# AS3364_bus_mixer_v1_0.net
KiCad netlist of a schematic drawn in EAGLE
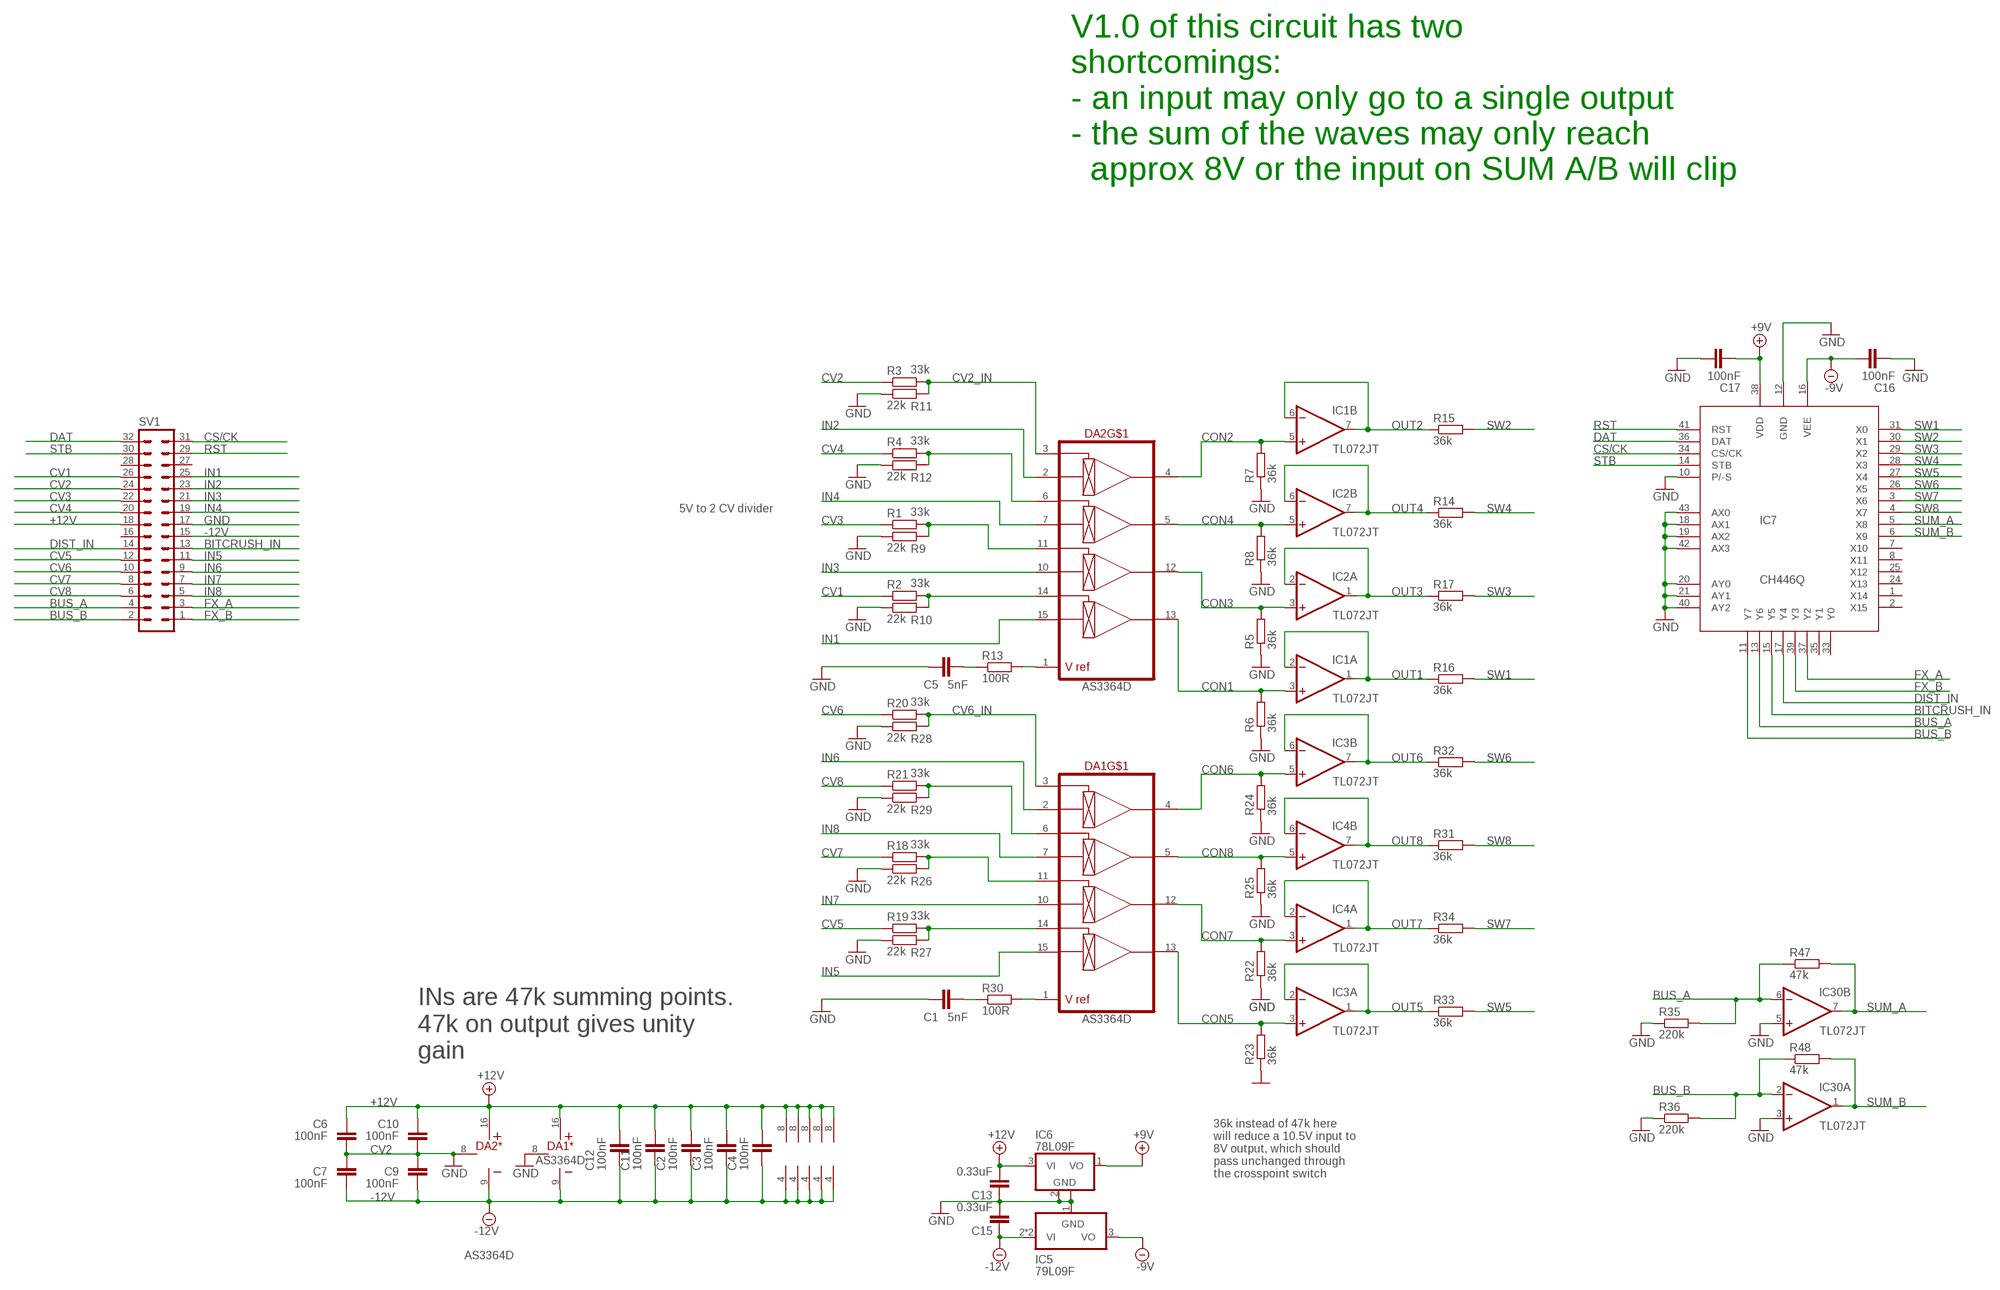
[diagram p0: schematic, sheet 1]

(export (version "E")
  (design (tool "Eeschema 10.0.6"))
  (components
    (comp (ref "C1")
      (value "5nF")
      (footprint "eagle-import:C0402")
      (libsource (lib "eagle-import") (part "C-EUC0402"))
    )
    (comp (ref "C2")
      (value "100nF")
      (footprint "eagle-import:C0402")
      (libsource (lib "eagle-import") (part "C-EUC0402"))
    )
    (comp (ref "C3")
      (value "100nF")
      (footprint "eagle-import:C0402")
      (libsource (lib "eagle-import") (part "C-EUC0402"))
    )
    (comp (ref "C4")
      (value "100nF")
      (footprint "eagle-import:C0402")
      (libsource (lib "eagle-import") (part "C-EUC0402"))
    )
    (comp (ref "C5")
      (value "5nF")
      (footprint "eagle-import:C0402")
      (libsource (lib "eagle-import") (part "C-EUC0402"))
    )
    (comp (ref "C6")
      (value "100nF")
      (footprint "eagle-import:C0402")
      (libsource (lib "eagle-import") (part "C-EUC0402"))
    )
    (comp (ref "C7")
      (value "100nF")
      (footprint "eagle-import:C0402")
      (libsource (lib "eagle-import") (part "C-EUC0402"))
    )
    (comp (ref "C9")
      (value "100nF")
      (footprint "eagle-import:C0402")
      (libsource (lib "eagle-import") (part "C-EUC0402"))
    )
    (comp (ref "C10")
      (value "100nF")
      (footprint "eagle-import:C0402")
      (libsource (lib "eagle-import") (part "C-EUC0402"))
    )
    (comp (ref "C11")
      (value "100nF")
      (footprint "eagle-import:C0402")
      (libsource (lib "eagle-import") (part "C-EUC0402"))
    )
    (comp (ref "C12")
      (value "100nF")
      (footprint "eagle-import:C0402")
      (libsource (lib "eagle-import") (part "C-EUC0402"))
    )
    (comp (ref "C13")
      (value "0.33uF")
      (footprint "eagle-import:C0603")
      (libsource (lib "eagle-import") (part "resistor_C-EUC0603"))
    )
    (comp (ref "C15")
      (value "0.33uF")
      (footprint "eagle-import:C0603")
      (libsource (lib "eagle-import") (part "resistor_C-EUC0603"))
    )
    (comp (ref "C16")
      (value "100nF")
      (footprint "eagle-import:C0402")
      (libsource (lib "eagle-import") (part "C-EUC0402"))
    )
    (comp (ref "C17")
      (value "100nF")
      (footprint "eagle-import:C0402")
      (libsource (lib "eagle-import") (part "C-EUC0402"))
    )
    (comp (ref "DA1")
      (value "AS3364D")
      (footprint "eagle-import:DIL16J")
      (libsource (lib "eagle-import") (part "AS3364D"))
    )
    (comp (ref "DA2")
      (value "AS3364D")
      (footprint "eagle-import:DIL16J")
      (libsource (lib "eagle-import") (part "AS3364D"))
    )
    (comp (ref "IC1")
      (value "TL072JT")
      (footprint "eagle-import:TSSOP8J")
      (libsource (lib "eagle-import") (part "TL072JT"))
    )
    (comp (ref "IC2")
      (value "TL072JT")
      (footprint "eagle-import:TSSOP8J")
      (libsource (lib "eagle-import") (part "TL072JT"))
    )
    (comp (ref "IC3")
      (value "TL072JT")
      (footprint "eagle-import:TSSOP8J")
      (libsource (lib "eagle-import") (part "TL072JT"))
    )
    (comp (ref "IC4")
      (value "TL072JT")
      (footprint "eagle-import:TSSOP8J")
      (libsource (lib "eagle-import") (part "TL072JT"))
    )
    (comp (ref "IC5")
      (value "79L09F")
      (footprint "eagle-import:SOT89")
      (libsource (lib "eagle-import") (part "79LF09"))
    )
    (comp (ref "IC6")
      (value "78L09F")
      (footprint "eagle-import:SOT89")
      (libsource (lib "eagle-import") (part "78LF09"))
    )
    (comp (ref "IC7")
      (value "CH446Q")
      (footprint "eagle-import:LQFP-44-J")
      (libsource (lib "eagle-import") (part "CH446Q"))
    )
    (comp (ref "IC30")
      (value "TL072JT")
      (footprint "eagle-import:TSSOP8J")
      (libsource (lib "eagle-import") (part "TL072JT"))
    )
    (comp (ref "R1")
      (value "33k")
      (footprint "eagle-import:R0402")
      (libsource (lib "eagle-import") (part "R-EU_R0402"))
    )
    (comp (ref "R2")
      (value "33k")
      (footprint "eagle-import:R0402")
      (libsource (lib "eagle-import") (part "R-EU_R0402"))
    )
    (comp (ref "R3")
      (value "33k")
      (footprint "eagle-import:R0402")
      (libsource (lib "eagle-import") (part "R-EU_R0402"))
    )
    (comp (ref "R4")
      (value "33k")
      (footprint "eagle-import:R0402")
      (libsource (lib "eagle-import") (part "R-EU_R0402"))
    )
    (comp (ref "R5")
      (value "36k")
      (footprint "eagle-import:R0402")
      (libsource (lib "eagle-import") (part "R-EU_R0402"))
    )
    (comp (ref "R6")
      (value "36k")
      (footprint "eagle-import:R0402")
      (libsource (lib "eagle-import") (part "R-EU_R0402"))
    )
    (comp (ref "R7")
      (value "36k")
      (footprint "eagle-import:R0402")
      (libsource (lib "eagle-import") (part "R-EU_R0402"))
    )
    (comp (ref "R8")
      (value "36k")
      (footprint "eagle-import:R0402")
      (libsource (lib "eagle-import") (part "R-EU_R0402"))
    )
    (comp (ref "R9")
      (value "22k")
      (footprint "eagle-import:R0402")
      (libsource (lib "eagle-import") (part "R-EU_R0402"))
    )
    (comp (ref "R10")
      (value "22k")
      (footprint "eagle-import:R0402")
      (libsource (lib "eagle-import") (part "R-EU_R0402"))
    )
    (comp (ref "R11")
      (value "22k")
      (footprint "eagle-import:R0402")
      (libsource (lib "eagle-import") (part "R-EU_R0402"))
    )
    (comp (ref "R12")
      (value "22k")
      (footprint "eagle-import:R0402")
      (libsource (lib "eagle-import") (part "R-EU_R0402"))
    )
    (comp (ref "R13")
      (value "100R")
      (footprint "eagle-import:R0402")
      (libsource (lib "eagle-import") (part "R-EU_R0402"))
    )
    (comp (ref "R14")
      (value "36k")
      (footprint "eagle-import:R0402")
      (libsource (lib "eagle-import") (part "R-EU_R0402"))
    )
    (comp (ref "R15")
      (value "36k")
      (footprint "eagle-import:R0402")
      (libsource (lib "eagle-import") (part "R-EU_R0402"))
    )
    (comp (ref "R16")
      (value "36k")
      (footprint "eagle-import:R0402")
      (libsource (lib "eagle-import") (part "R-EU_R0402"))
    )
    (comp (ref "R17")
      (value "36k")
      (footprint "eagle-import:R0402")
      (libsource (lib "eagle-import") (part "R-EU_R0402"))
    )
    (comp (ref "R18")
      (value "33k")
      (footprint "eagle-import:R0402")
      (libsource (lib "eagle-import") (part "R-EU_R0402"))
    )
    (comp (ref "R19")
      (value "33k")
      (footprint "eagle-import:R0402")
      (libsource (lib "eagle-import") (part "R-EU_R0402"))
    )
    (comp (ref "R20")
      (value "33k")
      (footprint "eagle-import:R0402")
      (libsource (lib "eagle-import") (part "R-EU_R0402"))
    )
    (comp (ref "R21")
      (value "33k")
      (footprint "eagle-import:R0402")
      (libsource (lib "eagle-import") (part "R-EU_R0402"))
    )
    (comp (ref "R22")
      (value "36k")
      (footprint "eagle-import:R0402")
      (libsource (lib "eagle-import") (part "R-EU_R0402"))
    )
    (comp (ref "R23")
      (value "36k")
      (footprint "eagle-import:R0402")
      (libsource (lib "eagle-import") (part "R-EU_R0402"))
    )
    (comp (ref "R24")
      (value "36k")
      (footprint "eagle-import:R0402")
      (libsource (lib "eagle-import") (part "R-EU_R0402"))
    )
    (comp (ref "R25")
      (value "36k")
      (footprint "eagle-import:R0402")
      (libsource (lib "eagle-import") (part "R-EU_R0402"))
    )
    (comp (ref "R26")
      (value "22k")
      (footprint "eagle-import:R0402")
      (libsource (lib "eagle-import") (part "R-EU_R0402"))
    )
    (comp (ref "R27")
      (value "22k")
      (footprint "eagle-import:R0402")
      (libsource (lib "eagle-import") (part "R-EU_R0402"))
    )
    (comp (ref "R28")
      (value "22k")
      (footprint "eagle-import:R0402")
      (libsource (lib "eagle-import") (part "R-EU_R0402"))
    )
    (comp (ref "R29")
      (value "22k")
      (footprint "eagle-import:R0402")
      (libsource (lib "eagle-import") (part "R-EU_R0402"))
    )
    (comp (ref "R30")
      (value "100R")
      (footprint "eagle-import:R0402")
      (libsource (lib "eagle-import") (part "R-EU_R0402"))
    )
    (comp (ref "R31")
      (value "36k")
      (footprint "eagle-import:R0402")
      (libsource (lib "eagle-import") (part "R-EU_R0402"))
    )
    (comp (ref "R32")
      (value "36k")
      (footprint "eagle-import:R0402")
      (libsource (lib "eagle-import") (part "R-EU_R0402"))
    )
    (comp (ref "R33")
      (value "36k")
      (footprint "eagle-import:R0402")
      (libsource (lib "eagle-import") (part "R-EU_R0402"))
    )
    (comp (ref "R34")
      (value "36k")
      (footprint "eagle-import:R0402")
      (libsource (lib "eagle-import") (part "R-EU_R0402"))
    )
    (comp (ref "R35")
      (value "220k")
      (footprint "eagle-import:R0402")
      (libsource (lib "eagle-import") (part "R-EU_R0402"))
    )
    (comp (ref "R36")
      (value "220k")
      (footprint "eagle-import:R0402")
      (libsource (lib "eagle-import") (part "R-EU_R0402"))
    )
    (comp (ref "R47")
      (value "47k")
      (footprint "eagle-import:R0402")
      (libsource (lib "eagle-import") (part "R-EU_R0402"))
    )
    (comp (ref "R48")
      (value "47k")
      (footprint "eagle-import:R0402")
      (libsource (lib "eagle-import") (part "R-EU_R0402"))
    )
    (comp (ref "SV1")
      (value "MA16-2WJ")
      (footprint "eagle-import:MA16-2WJ")
      (libsource (lib "eagle-import") (part "MA16-2WJ"))
    )
  )
  (nets
    (net (code "1") (name "+9V") (class "Default")
      (node (ref "C17") (pin "1") (pinfunction "1_1") (pintype "passive"))
      (node (ref "IC6") (pin "1") (pinfunction "VO_1") (pintype "passive"))
      (node (ref "IC7") (pin "38") (pinfunction "VDD_38") (pintype "power_in"))
    )
    (net (code "2") (name "+12V") (class "Default")
      (node (ref "C10") (pin "2") (pinfunction "2_2") (pintype "passive"))
      (node (ref "C11") (pin "2") (pinfunction "2_2") (pintype "passive"))
      (node (ref "C12") (pin "2") (pinfunction "2_2") (pintype "passive"))
      (node (ref "C13") (pin "2") (pinfunction "2_2") (pintype "passive"))
      (node (ref "C2") (pin "2") (pinfunction "2_2") (pintype "passive"))
      (node (ref "C3") (pin "2") (pinfunction "2_2") (pintype "passive"))
      (node (ref "C4") (pin "2") (pinfunction "2_2") (pintype "passive"))
      (node (ref "C6") (pin "2") (pinfunction "2_2") (pintype "passive"))
      (node (ref "DA1") (pin "16") (pinfunction "V+_16") (pintype "power_in"))
      (node (ref "DA2") (pin "16") (pinfunction "V+_16") (pintype "power_in"))
      (node (ref "IC1") (pin "8") (pinfunction "V+_8") (pintype "power_in"))
      (node (ref "IC2") (pin "8") (pinfunction "V+_8") (pintype "power_in"))
      (node (ref "IC3") (pin "8") (pinfunction "V+_8") (pintype "power_in"))
      (node (ref "IC30") (pin "8") (pinfunction "V+_8") (pintype "power_in"))
      (node (ref "IC4") (pin "8") (pinfunction "V+_8") (pintype "power_in"))
      (node (ref "IC6") (pin "3") (pinfunction "VI_3") (pintype "input"))
      (node (ref "SV1") (pin "18") (pinfunction "18_18") (pintype "passive"))
    )
    (net (code "3") (name "-9V") (class "Default")
      (node (ref "C16") (pin "2") (pinfunction "2_2") (pintype "passive"))
      (node (ref "IC5") (pin "3") (pinfunction "VO_3") (pintype "passive"))
      (node (ref "IC7") (pin "16") (pinfunction "VEE_16") (pintype "power_in"))
    )
    (net (code "4") (name "-12V") (class "Default")
      (node (ref "C11") (pin "1") (pinfunction "1_1") (pintype "passive"))
      (node (ref "C12") (pin "1") (pinfunction "1_1") (pintype "passive"))
      (node (ref "C15") (pin "1") (pinfunction "1_1") (pintype "passive"))
      (node (ref "C2") (pin "1") (pinfunction "1_1") (pintype "passive"))
      (node (ref "C3") (pin "1") (pinfunction "1_1") (pintype "passive"))
      (node (ref "C4") (pin "1") (pinfunction "1_1") (pintype "passive"))
      (node (ref "C7") (pin "1") (pinfunction "1_1") (pintype "passive"))
      (node (ref "C9") (pin "1") (pinfunction "1_1") (pintype "passive"))
      (node (ref "DA1") (pin "9") (pinfunction "V-_9") (pintype "power_in"))
      (node (ref "DA2") (pin "9") (pinfunction "V-_9") (pintype "power_in"))
      (node (ref "IC1") (pin "4") (pinfunction "V-_4") (pintype "power_in"))
      (node (ref "IC2") (pin "4") (pinfunction "V-_4") (pintype "power_in"))
      (node (ref "IC3") (pin "4") (pinfunction "V-_4") (pintype "power_in"))
      (node (ref "IC30") (pin "4") (pinfunction "V-_4") (pintype "power_in"))
      (node (ref "IC4") (pin "4") (pinfunction "V-_4") (pintype "power_in"))
      (node (ref "IC5") (pin "2") (pinfunction "VI_2") (pintype "input"))
      (node (ref "IC5") (pin "2@1") (pinfunction "VI_2@1") (pintype "input"))
      (node (ref "SV1") (pin "15") (pinfunction "15_15") (pintype "passive"))
    )
    (net (code "5") (name "/BITCRUSH_IN") (class "Default")
      (node (ref "IC7") (pin "15") (pinfunction "Y5_15") (pintype "bidirectional"))
      (node (ref "SV1") (pin "13") (pinfunction "13_13") (pintype "passive"))
    )
    (net (code "6") (name "/BUS_A") (class "Default")
      (node (ref "IC30") (pin "6") (pinfunction "-IN_6") (pintype "input"))
      (node (ref "IC7") (pin "13") (pinfunction "Y6_13") (pintype "bidirectional"))
      (node (ref "R35") (pin "2") (pinfunction "2_2") (pintype "passive"))
      (node (ref "R47") (pin "1") (pinfunction "1_1") (pintype "passive"))
      (node (ref "SV1") (pin "4") (pinfunction "4_4") (pintype "passive"))
    )
    (net (code "7") (name "/BUS_B") (class "Default")
      (node (ref "IC30") (pin "2") (pinfunction "-IN_2") (pintype "input"))
      (node (ref "IC7") (pin "11") (pinfunction "Y7_11") (pintype "bidirectional"))
      (node (ref "R36") (pin "2") (pinfunction "2_2") (pintype "passive"))
      (node (ref "R48") (pin "1") (pinfunction "1_1") (pintype "passive"))
      (node (ref "SV1") (pin "2") (pinfunction "2_2") (pintype "passive"))
    )
    (net (code "8") (name "/CON1") (class "Default")
      (node (ref "DA2") (pin "13") (pinfunction "OUT4_13") (pintype "output"))
      (node (ref "IC1") (pin "3") (pinfunction "+IN_3") (pintype "input"))
      (node (ref "R6") (pin "2") (pinfunction "2_2") (pintype "passive"))
    )
    (net (code "9") (name "/CON2") (class "Default")
      (node (ref "DA2") (pin "4") (pinfunction "OUT1_4") (pintype "output"))
      (node (ref "IC1") (pin "5") (pinfunction "+IN_5") (pintype "input"))
      (node (ref "R7") (pin "2") (pinfunction "2_2") (pintype "passive"))
    )
    (net (code "10") (name "/CON3") (class "Default")
      (node (ref "DA2") (pin "12") (pinfunction "OUT3_12") (pintype "output"))
      (node (ref "IC2") (pin "3") (pinfunction "+IN_3") (pintype "input"))
      (node (ref "R5") (pin "2") (pinfunction "2_2") (pintype "passive"))
    )
    (net (code "11") (name "/CON4") (class "Default")
      (node (ref "DA2") (pin "5") (pinfunction "OUT2_5") (pintype "output"))
      (node (ref "IC2") (pin "5") (pinfunction "+IN_5") (pintype "input"))
      (node (ref "R8") (pin "2") (pinfunction "2_2") (pintype "passive"))
    )
    (net (code "12") (name "/CON5") (class "Default")
      (node (ref "DA1") (pin "13") (pinfunction "OUT4_13") (pintype "output"))
      (node (ref "IC3") (pin "3") (pinfunction "+IN_3") (pintype "input"))
      (node (ref "R23") (pin "2") (pinfunction "2_2") (pintype "passive"))
    )
    (net (code "13") (name "/CON6") (class "Default")
      (node (ref "DA1") (pin "4") (pinfunction "OUT1_4") (pintype "output"))
      (node (ref "IC3") (pin "5") (pinfunction "+IN_5") (pintype "input"))
      (node (ref "R24") (pin "2") (pinfunction "2_2") (pintype "passive"))
    )
    (net (code "14") (name "/CON7") (class "Default")
      (node (ref "DA1") (pin "12") (pinfunction "OUT3_12") (pintype "output"))
      (node (ref "IC4") (pin "3") (pinfunction "+IN_3") (pintype "input"))
      (node (ref "R22") (pin "2") (pinfunction "2_2") (pintype "passive"))
    )
    (net (code "15") (name "/CON8") (class "Default")
      (node (ref "DA1") (pin "5") (pinfunction "OUT2_5") (pintype "output"))
      (node (ref "IC4") (pin "5") (pinfunction "+IN_5") (pintype "input"))
      (node (ref "R25") (pin "2") (pinfunction "2_2") (pintype "passive"))
    )
    (net (code "16") (name "/CS{slash}CK") (class "Default")
      (node (ref "IC7") (pin "34") (pinfunction "CS/CK_34") (pintype "bidirectional"))
      (node (ref "SV1") (pin "31") (pinfunction "31_31") (pintype "passive"))
    )
    (net (code "17") (name "/CV1") (class "Default")
      (node (ref "R2") (pin "1") (pinfunction "1_1") (pintype "passive"))
      (node (ref "SV1") (pin "26") (pinfunction "26_26") (pintype "passive"))
    )
    (net (code "18") (name "/CV2") (class "Default")
      (node (ref "R3") (pin "1") (pinfunction "1_1") (pintype "passive"))
      (node (ref "SV1") (pin "24") (pinfunction "24_24") (pintype "passive"))
    )
    (net (code "19") (name "/CV2_IN") (class "Default")
      (node (ref "DA2") (pin "3") (pinfunction "CV1_3") (pintype "input"))
      (node (ref "R11") (pin "2") (pinfunction "2_2") (pintype "passive"))
      (node (ref "R3") (pin "2") (pinfunction "2_2") (pintype "passive"))
    )
    (net (code "20") (name "/CV3") (class "Default")
      (node (ref "R1") (pin "1") (pinfunction "1_1") (pintype "passive"))
      (node (ref "SV1") (pin "22") (pinfunction "22_22") (pintype "passive"))
    )
    (net (code "21") (name "/CV4") (class "Default")
      (node (ref "R4") (pin "1") (pinfunction "1_1") (pintype "passive"))
      (node (ref "SV1") (pin "20") (pinfunction "20_20") (pintype "passive"))
    )
    (net (code "22") (name "/CV5") (class "Default")
      (node (ref "R19") (pin "1") (pinfunction "1_1") (pintype "passive"))
      (node (ref "SV1") (pin "12") (pinfunction "12_12") (pintype "passive"))
    )
    (net (code "23") (name "/CV6") (class "Default")
      (node (ref "R20") (pin "1") (pinfunction "1_1") (pintype "passive"))
      (node (ref "SV1") (pin "10") (pinfunction "10_10") (pintype "passive"))
    )
    (net (code "24") (name "/CV6_IN") (class "Default")
      (node (ref "DA1") (pin "3") (pinfunction "CV1_3") (pintype "input"))
      (node (ref "R20") (pin "2") (pinfunction "2_2") (pintype "passive"))
      (node (ref "R28") (pin "2") (pinfunction "2_2") (pintype "passive"))
    )
    (net (code "25") (name "/CV7") (class "Default")
      (node (ref "R18") (pin "1") (pinfunction "1_1") (pintype "passive"))
      (node (ref "SV1") (pin "8") (pinfunction "8_8") (pintype "passive"))
    )
    (net (code "26") (name "/CV8") (class "Default")
      (node (ref "R21") (pin "1") (pinfunction "1_1") (pintype "passive"))
      (node (ref "SV1") (pin "6") (pinfunction "6_6") (pintype "passive"))
    )
    (net (code "27") (name "/DAT") (class "Default")
      (node (ref "IC7") (pin "36") (pinfunction "DAT_36") (pintype "bidirectional"))
      (node (ref "SV1") (pin "32") (pinfunction "32_32") (pintype "passive"))
    )
    (net (code "28") (name "/DIST_IN") (class "Default")
      (node (ref "IC7") (pin "17") (pinfunction "Y4_17") (pintype "bidirectional"))
      (node (ref "SV1") (pin "14") (pinfunction "14_14") (pintype "passive"))
    )
    (net (code "29") (name "/FX_A") (class "Default")
      (node (ref "IC7") (pin "37") (pinfunction "Y2_37") (pintype "bidirectional"))
      (node (ref "SV1") (pin "3") (pinfunction "3_3") (pintype "passive"))
    )
    (net (code "30") (name "/FX_B") (class "Default")
      (node (ref "IC7") (pin "39") (pinfunction "Y3_39") (pintype "bidirectional"))
      (node (ref "SV1") (pin "1") (pinfunction "1_1") (pintype "passive"))
    )
    (net (code "31") (name "/IN1") (class "Default")
      (node (ref "DA2") (pin "15") (pinfunction "IN4_15") (pintype "input"))
      (node (ref "SV1") (pin "25") (pinfunction "25_25") (pintype "passive"))
    )
    (net (code "32") (name "/IN2") (class "Default")
      (node (ref "DA2") (pin "2") (pinfunction "IN1_2") (pintype "input"))
      (node (ref "SV1") (pin "23") (pinfunction "23_23") (pintype "passive"))
    )
    (net (code "33") (name "/IN3") (class "Default")
      (node (ref "DA2") (pin "10") (pinfunction "IN3_10") (pintype "input"))
      (node (ref "SV1") (pin "21") (pinfunction "21_21") (pintype "passive"))
    )
    (net (code "34") (name "/IN4") (class "Default")
      (node (ref "DA2") (pin "7") (pinfunction "IN2_7") (pintype "input"))
      (node (ref "SV1") (pin "19") (pinfunction "19_19") (pintype "passive"))
    )
    (net (code "35") (name "/IN5") (class "Default")
      (node (ref "DA1") (pin "15") (pinfunction "IN4_15") (pintype "input"))
      (node (ref "SV1") (pin "11") (pinfunction "11_11") (pintype "passive"))
    )
    (net (code "36") (name "/IN6") (class "Default")
      (node (ref "DA1") (pin "2") (pinfunction "IN1_2") (pintype "input"))
      (node (ref "SV1") (pin "9") (pinfunction "9_9") (pintype "passive"))
    )
    (net (code "37") (name "/IN7") (class "Default")
      (node (ref "DA1") (pin "10") (pinfunction "IN3_10") (pintype "input"))
      (node (ref "SV1") (pin "7") (pinfunction "7_7") (pintype "passive"))
    )
    (net (code "38") (name "/IN8") (class "Default")
      (node (ref "DA1") (pin "7") (pinfunction "IN2_7") (pintype "input"))
      (node (ref "SV1") (pin "5") (pinfunction "5_5") (pintype "passive"))
    )
    (net (code "39") (name "/OUT1") (class "Default")
      (node (ref "IC1") (pin "1") (pinfunction "OUT_1") (pintype "output"))
      (node (ref "IC1") (pin "2") (pinfunction "-IN_2") (pintype "input"))
      (node (ref "R16") (pin "1") (pinfunction "1_1") (pintype "passive"))
    )
    (net (code "40") (name "/OUT2") (class "Default")
      (node (ref "IC1") (pin "6") (pinfunction "-IN_6") (pintype "input"))
      (node (ref "IC1") (pin "7") (pinfunction "OUT_7") (pintype "output"))
      (node (ref "R15") (pin "1") (pinfunction "1_1") (pintype "passive"))
    )
    (net (code "41") (name "/OUT3") (class "Default")
      (node (ref "IC2") (pin "1") (pinfunction "OUT_1") (pintype "output"))
      (node (ref "IC2") (pin "2") (pinfunction "-IN_2") (pintype "input"))
      (node (ref "R17") (pin "1") (pinfunction "1_1") (pintype "passive"))
    )
    (net (code "42") (name "/OUT4") (class "Default")
      (node (ref "IC2") (pin "6") (pinfunction "-IN_6") (pintype "input"))
      (node (ref "IC2") (pin "7") (pinfunction "OUT_7") (pintype "output"))
      (node (ref "R14") (pin "1") (pinfunction "1_1") (pintype "passive"))
    )
    (net (code "43") (name "/OUT5") (class "Default")
      (node (ref "IC3") (pin "1") (pinfunction "OUT_1") (pintype "output"))
      (node (ref "IC3") (pin "2") (pinfunction "-IN_2") (pintype "input"))
      (node (ref "R33") (pin "1") (pinfunction "1_1") (pintype "passive"))
    )
    (net (code "44") (name "/OUT6") (class "Default")
      (node (ref "IC3") (pin "6") (pinfunction "-IN_6") (pintype "input"))
      (node (ref "IC3") (pin "7") (pinfunction "OUT_7") (pintype "output"))
      (node (ref "R32") (pin "1") (pinfunction "1_1") (pintype "passive"))
    )
    (net (code "45") (name "/OUT7") (class "Default")
      (node (ref "IC4") (pin "1") (pinfunction "OUT_1") (pintype "output"))
      (node (ref "IC4") (pin "2") (pinfunction "-IN_2") (pintype "input"))
      (node (ref "R34") (pin "1") (pinfunction "1_1") (pintype "passive"))
    )
    (net (code "46") (name "/OUT8") (class "Default")
      (node (ref "IC4") (pin "6") (pinfunction "-IN_6") (pintype "input"))
      (node (ref "IC4") (pin "7") (pinfunction "OUT_7") (pintype "output"))
      (node (ref "R31") (pin "1") (pinfunction "1_1") (pintype "passive"))
    )
    (net (code "47") (name "/RST") (class "Default")
      (node (ref "IC7") (pin "41") (pinfunction "RST_41") (pintype "bidirectional"))
      (node (ref "SV1") (pin "29") (pinfunction "29_29") (pintype "passive"))
    )
    (net (code "48") (name "/STB") (class "Default")
      (node (ref "IC7") (pin "14") (pinfunction "STB_14") (pintype "bidirectional"))
      (node (ref "SV1") (pin "30") (pinfunction "30_30") (pintype "passive"))
    )
    (net (code "49") (name "/SUM_A") (class "Default")
      (node (ref "IC30") (pin "7") (pinfunction "OUT_7") (pintype "output"))
      (node (ref "IC7") (pin "5") (pinfunction "X8_5") (pintype "bidirectional"))
      (node (ref "R47") (pin "2") (pinfunction "2_2") (pintype "passive"))
    )
    (net (code "50") (name "/SUM_B") (class "Default")
      (node (ref "IC30") (pin "1") (pinfunction "OUT_1") (pintype "output"))
      (node (ref "IC7") (pin "6") (pinfunction "X9_6") (pintype "bidirectional"))
      (node (ref "R48") (pin "2") (pinfunction "2_2") (pintype "passive"))
    )
    (net (code "51") (name "/SW1") (class "Default")
      (node (ref "IC7") (pin "31") (pinfunction "X0_31") (pintype "bidirectional"))
      (node (ref "R16") (pin "2") (pinfunction "2_2") (pintype "passive"))
    )
    (net (code "52") (name "/SW2") (class "Default")
      (node (ref "IC7") (pin "30") (pinfunction "X1_30") (pintype "bidirectional"))
      (node (ref "R15") (pin "2") (pinfunction "2_2") (pintype "passive"))
    )
    (net (code "53") (name "/SW3") (class "Default")
      (node (ref "IC7") (pin "29") (pinfunction "X2_29") (pintype "bidirectional"))
      (node (ref "R17") (pin "2") (pinfunction "2_2") (pintype "passive"))
    )
    (net (code "54") (name "/SW4") (class "Default")
      (node (ref "IC7") (pin "28") (pinfunction "X3_28") (pintype "bidirectional"))
      (node (ref "R14") (pin "2") (pinfunction "2_2") (pintype "passive"))
    )
    (net (code "55") (name "/SW5") (class "Default")
      (node (ref "IC7") (pin "27") (pinfunction "X4_27") (pintype "bidirectional"))
      (node (ref "R33") (pin "2") (pinfunction "2_2") (pintype "passive"))
    )
    (net (code "56") (name "/SW6") (class "Default")
      (node (ref "IC7") (pin "26") (pinfunction "X5_26") (pintype "bidirectional"))
      (node (ref "R32") (pin "2") (pinfunction "2_2") (pintype "passive"))
    )
    (net (code "57") (name "/SW7") (class "Default")
      (node (ref "IC7") (pin "3") (pinfunction "X6_3") (pintype "bidirectional"))
      (node (ref "R34") (pin "2") (pinfunction "2_2") (pintype "passive"))
    )
    (net (code "58") (name "/SW8") (class "Default")
      (node (ref "IC7") (pin "4") (pinfunction "X7_4") (pintype "bidirectional"))
      (node (ref "R31") (pin "2") (pinfunction "2_2") (pintype "passive"))
    )
    (net (code "59") (name "GND") (class "Default")
      (node (ref "C1") (pin "1") (pinfunction "1_1") (pintype "passive"))
      (node (ref "C10") (pin "1") (pinfunction "1_1") (pintype "passive"))
      (node (ref "C13") (pin "1") (pinfunction "1_1") (pintype "passive"))
      (node (ref "C15") (pin "2") (pinfunction "2_2") (pintype "passive"))
      (node (ref "C16") (pin "1") (pinfunction "1_1") (pintype "passive"))
      (node (ref "C17") (pin "2") (pinfunction "2_2") (pintype "passive"))
      (node (ref "C5") (pin "1") (pinfunction "1_1") (pintype "passive"))
      (node (ref "C6") (pin "1") (pinfunction "1_1") (pintype "passive"))
      (node (ref "C7") (pin "2") (pinfunction "2_2") (pintype "passive"))
      (node (ref "C9") (pin "2") (pinfunction "2_2") (pintype "passive"))
      (node (ref "DA1") (pin "8") (pinfunction "GND_8") (pintype "power_in"))
      (node (ref "DA2") (pin "8") (pinfunction "GND_8") (pintype "power_in"))
      (node (ref "IC30") (pin "3") (pinfunction "+IN_3") (pintype "input"))
      (node (ref "IC30") (pin "5") (pinfunction "+IN_5") (pintype "input"))
      (node (ref "IC5") (pin "1") (pinfunction "GND_1") (pintype "passive"))
      (node (ref "IC6") (pin "2") (pinfunction "GND_2") (pintype "passive"))
      (node (ref "IC6") (pin "2@1") (pinfunction "GND_2@1") (pintype "passive"))
      (node (ref "IC7") (pin "10") (pinfunction "P/-S_10") (pintype "bidirectional"))
      (node (ref "IC7") (pin "12") (pinfunction "GND_12") (pintype "power_in"))
      (node (ref "IC7") (pin "18") (pinfunction "AX1_18") (pintype "bidirectional"))
      (node (ref "IC7") (pin "19") (pinfunction "AX2_19") (pintype "bidirectional"))
      (node (ref "IC7") (pin "20") (pinfunction "AY0_20") (pintype "bidirectional"))
      (node (ref "IC7") (pin "21") (pinfunction "AY1_21") (pintype "bidirectional"))
      (node (ref "IC7") (pin "40") (pinfunction "AY2_40") (pintype "bidirectional"))
      (node (ref "IC7") (pin "42") (pinfunction "AX3_42") (pintype "bidirectional"))
      (node (ref "IC7") (pin "43") (pinfunction "AX0_43") (pintype "bidirectional"))
      (node (ref "R10") (pin "1") (pinfunction "1_1") (pintype "passive"))
      (node (ref "R11") (pin "1") (pinfunction "1_1") (pintype "passive"))
      (node (ref "R12") (pin "1") (pinfunction "1_1") (pintype "passive"))
      (node (ref "R22") (pin "1") (pinfunction "1_1") (pintype "passive"))
      (node (ref "R23") (pin "1") (pinfunction "1_1") (pintype "passive"))
      (node (ref "R24") (pin "1") (pinfunction "1_1") (pintype "passive"))
      (node (ref "R25") (pin "1") (pinfunction "1_1") (pintype "passive"))
      (node (ref "R26") (pin "1") (pinfunction "1_1") (pintype "passive"))
      (node (ref "R27") (pin "1") (pinfunction "1_1") (pintype "passive"))
      (node (ref "R28") (pin "1") (pinfunction "1_1") (pintype "passive"))
      (node (ref "R29") (pin "1") (pinfunction "1_1") (pintype "passive"))
      (node (ref "R35") (pin "1") (pinfunction "1_1") (pintype "passive"))
      (node (ref "R36") (pin "1") (pinfunction "1_1") (pintype "passive"))
      (node (ref "R5") (pin "1") (pinfunction "1_1") (pintype "passive"))
      (node (ref "R6") (pin "1") (pinfunction "1_1") (pintype "passive"))
      (node (ref "R7") (pin "1") (pinfunction "1_1") (pintype "passive"))
      (node (ref "R8") (pin "1") (pinfunction "1_1") (pintype "passive"))
      (node (ref "R9") (pin "1") (pinfunction "1_1") (pintype "passive"))
      (node (ref "SV1") (pin "17") (pinfunction "17_17") (pintype "passive"))
    )
    (net (code "60") (name "Net-(C1-Pad2)") (class "Default")
      (node (ref "C1") (pin "2") (pinfunction "2_2") (pintype "passive"))
      (node (ref "R30") (pin "1") (pinfunction "1_1") (pintype "passive"))
    )
    (net (code "61") (name "Net-(C5-Pad2)") (class "Default")
      (node (ref "C5") (pin "2") (pinfunction "2_2") (pintype "passive"))
      (node (ref "R13") (pin "1") (pinfunction "1_1") (pintype "passive"))
    )
    (net (code "62") (name "Net-(DA1B-CV2)") (class "Default")
      (node (ref "DA1") (pin "6") (pinfunction "CV2_6") (pintype "input"))
      (node (ref "R21") (pin "2") (pinfunction "2_2") (pintype "passive"))
      (node (ref "R29") (pin "2") (pinfunction "2_2") (pintype "passive"))
    )
    (net (code "63") (name "Net-(DA1B-CV3)") (class "Default")
      (node (ref "DA1") (pin "11") (pinfunction "CV3_11") (pintype "input"))
      (node (ref "R18") (pin "2") (pinfunction "2_2") (pintype "passive"))
      (node (ref "R26") (pin "2") (pinfunction "2_2") (pintype "passive"))
    )
    (net (code "64") (name "Net-(DA1B-CV4)") (class "Default")
      (node (ref "DA1") (pin "14") (pinfunction "CV4_14") (pintype "input"))
      (node (ref "R19") (pin "2") (pinfunction "2_2") (pintype "passive"))
      (node (ref "R27") (pin "2") (pinfunction "2_2") (pintype "passive"))
    )
    (net (code "65") (name "Net-(DA1B-VREF)") (class "Default")
      (node (ref "DA1") (pin "1") (pinfunction "VREF_1") (pintype "output"))
      (node (ref "R30") (pin "2") (pinfunction "2_2") (pintype "passive"))
    )
    (net (code "66") (name "Net-(DA2B-CV2)") (class "Default")
      (node (ref "DA2") (pin "6") (pinfunction "CV2_6") (pintype "input"))
      (node (ref "R12") (pin "2") (pinfunction "2_2") (pintype "passive"))
      (node (ref "R4") (pin "2") (pinfunction "2_2") (pintype "passive"))
    )
    (net (code "67") (name "Net-(DA2B-CV3)") (class "Default")
      (node (ref "DA2") (pin "11") (pinfunction "CV3_11") (pintype "input"))
      (node (ref "R1") (pin "2") (pinfunction "2_2") (pintype "passive"))
      (node (ref "R9") (pin "2") (pinfunction "2_2") (pintype "passive"))
    )
    (net (code "68") (name "Net-(DA2B-CV4)") (class "Default")
      (node (ref "DA2") (pin "14") (pinfunction "CV4_14") (pintype "input"))
      (node (ref "R10") (pin "2") (pinfunction "2_2") (pintype "passive"))
      (node (ref "R2") (pin "2") (pinfunction "2_2") (pintype "passive"))
    )
    (net (code "69") (name "Net-(DA2B-VREF)") (class "Default")
      (node (ref "DA2") (pin "1") (pinfunction "VREF_1") (pintype "output"))
      (node (ref "R13") (pin "2") (pinfunction "2_2") (pintype "passive"))
    )
    (net (code "70") (name "unconnected-(IC7-X10-Pad7)") (class "Default")
      (node (ref "IC7") (pin "7") (pinfunction "X10_7") (pintype "bidirectional"))
    )
    (net (code "71") (name "unconnected-(IC7-X11-Pad8)") (class "Default")
      (node (ref "IC7") (pin "8") (pinfunction "X11_8") (pintype "bidirectional"))
    )
    (net (code "72") (name "unconnected-(IC7-X12-Pad25)") (class "Default")
      (node (ref "IC7") (pin "25") (pinfunction "X12_25") (pintype "bidirectional"))
    )
    (net (code "73") (name "unconnected-(IC7-X13-Pad24)") (class "Default")
      (node (ref "IC7") (pin "24") (pinfunction "X13_24") (pintype "bidirectional"))
    )
    (net (code "74") (name "unconnected-(IC7-X14-Pad1)") (class "Default")
      (node (ref "IC7") (pin "1") (pinfunction "X14_1") (pintype "bidirectional"))
    )
    (net (code "75") (name "unconnected-(IC7-X15-Pad2)") (class "Default")
      (node (ref "IC7") (pin "2") (pinfunction "X15_2") (pintype "bidirectional"))
    )
    (net (code "76") (name "unconnected-(IC7-Y0-Pad33)") (class "Default")
      (node (ref "IC7") (pin "33") (pinfunction "Y0_33") (pintype "bidirectional"))
    )
    (net (code "77") (name "unconnected-(IC7-Y1-Pad35)") (class "Default")
      (node (ref "IC7") (pin "35") (pinfunction "Y1_35") (pintype "bidirectional"))
    )
    (net (code "78") (name "unconnected-(SV1-Pad16)") (class "Default")
      (node (ref "SV1") (pin "16") (pinfunction "16_16") (pintype "passive"))
    )
    (net (code "79") (name "unconnected-(SV1-Pad27)") (class "Default")
      (node (ref "SV1") (pin "27") (pinfunction "27_27") (pintype "passive"))
    )
    (net (code "80") (name "unconnected-(SV1-Pad28)") (class "Default")
      (node (ref "SV1") (pin "28") (pinfunction "28_28") (pintype "passive"))
    )
  )
)
